# big-muff.net
KiCad netlist of a schematic drawn in EAGLE
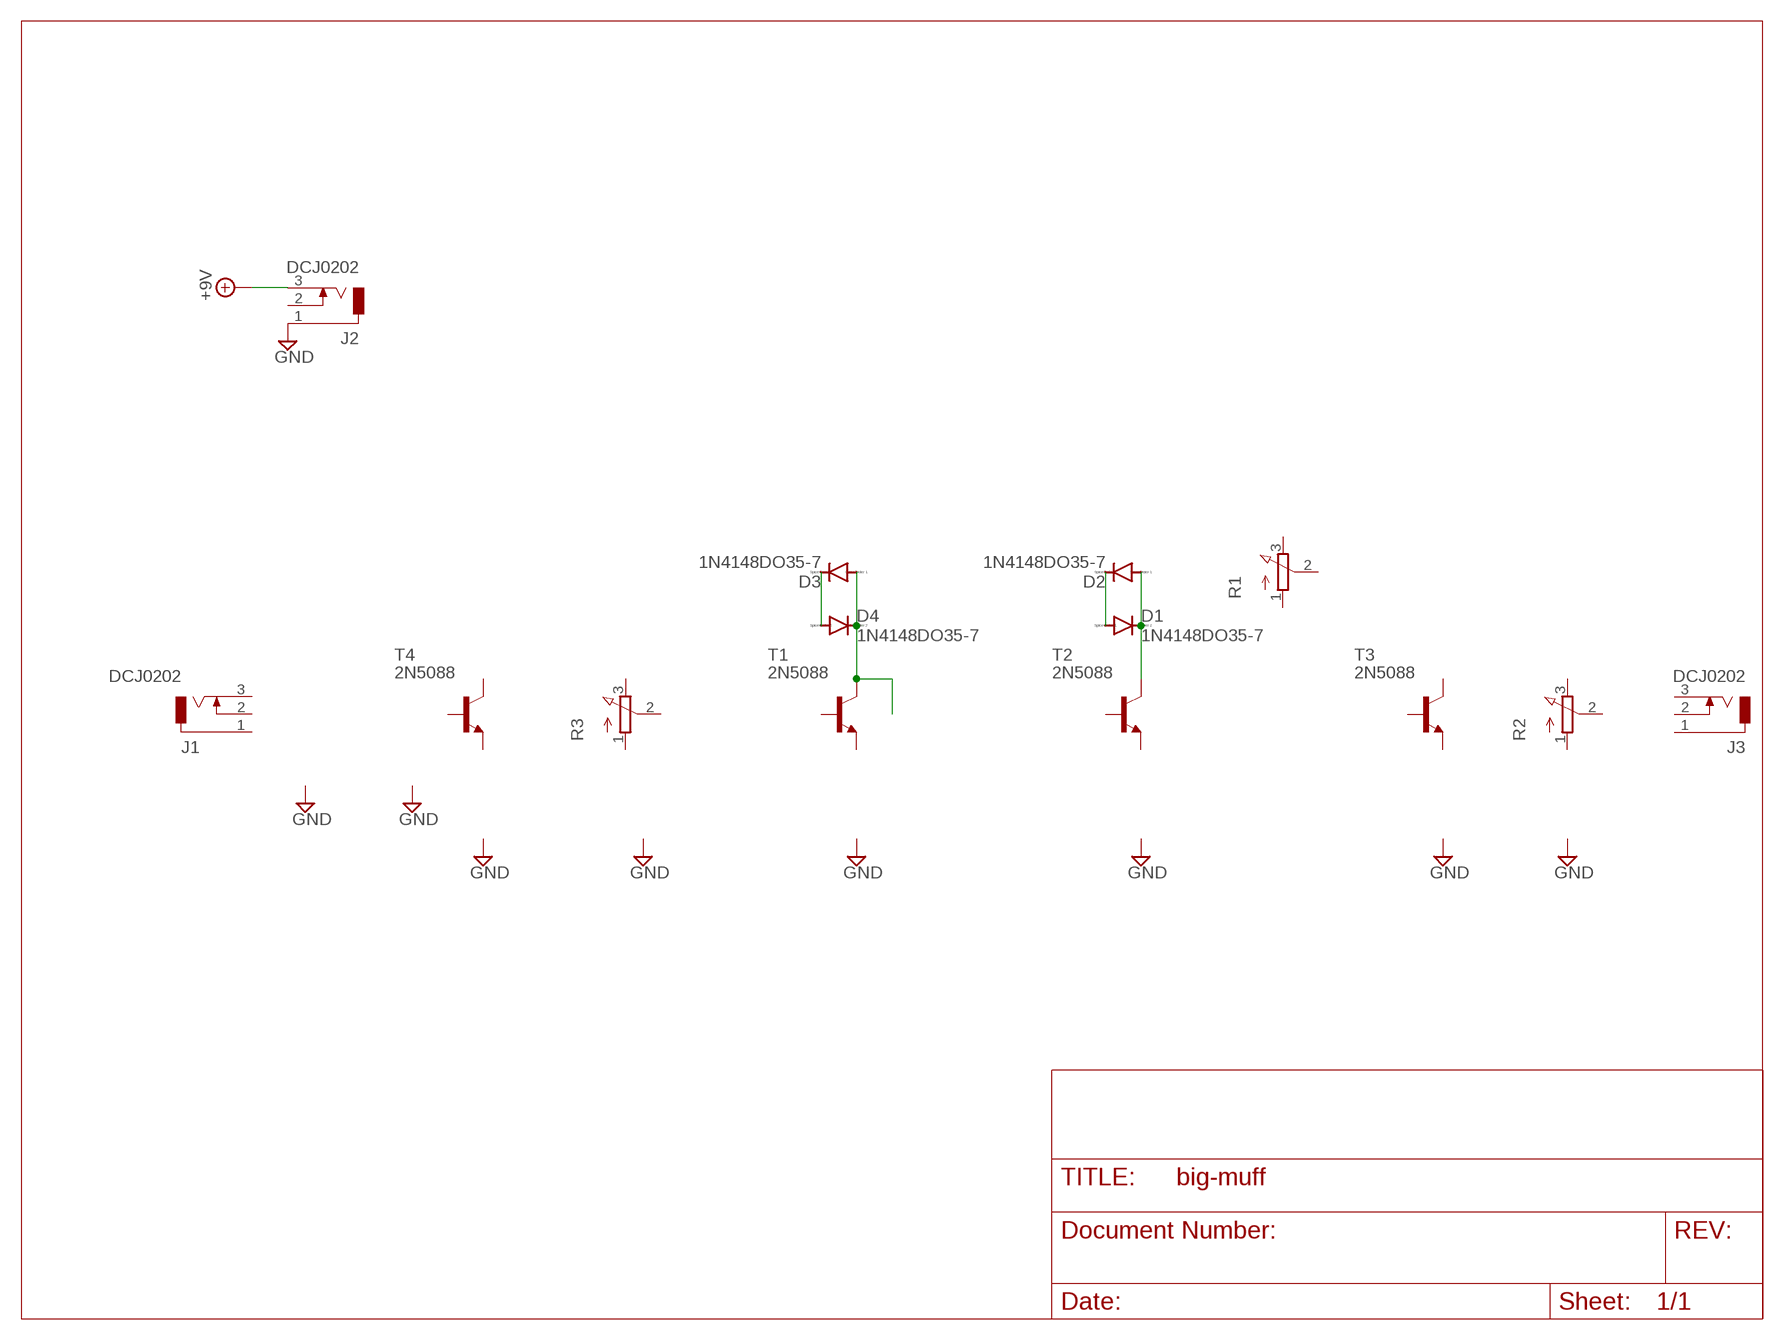
[diagram p0: schematic, sheet 1]

(export (version "E")
  (design (tool "Eeschema 10.0.6"))
  (components
    (comp (ref "D1")
      (value "1N4148DO35-7")
      (footprint "eagle-import:DO35-7")
      (libsource (lib "eagle-import") (part "1N4148DO35-7"))
    )
    (comp (ref "D2")
      (value "1N4148DO35-7")
      (footprint "eagle-import:DO35-7")
      (libsource (lib "eagle-import") (part "1N4148DO35-7"))
    )
    (comp (ref "D3")
      (value "1N4148DO35-7")
      (footprint "eagle-import:DO35-7")
      (libsource (lib "eagle-import") (part "1N4148DO35-7"))
    )
    (comp (ref "D4")
      (value "1N4148DO35-7")
      (footprint "eagle-import:DO35-7")
      (libsource (lib "eagle-import") (part "1N4148DO35-7"))
    )
    (comp (ref "J1")
      (value "DCJ0202")
      (footprint "eagle-import:DCJ0202")
      (libsource (lib "eagle-import") (part "DCJ0202"))
    )
    (comp (ref "J2")
      (value "DCJ0202")
      (footprint "eagle-import:DCJ0202")
      (libsource (lib "eagle-import") (part "DCJ0202"))
    )
    (comp (ref "J3")
      (value "DCJ0202")
      (footprint "eagle-import:DCJ0202")
      (libsource (lib "eagle-import") (part "DCJ0202"))
    )
    (comp (ref "R1")
      (value "3RP/1610N")
      (footprint "eagle-import:3RP_1610N")
      (libsource (lib "eagle-import") (part "3RP/1610N"))
    )
    (comp (ref "R2")
      (value "3RP/1610N")
      (footprint "eagle-import:3RP_1610N")
      (libsource (lib "eagle-import") (part "3RP/1610N"))
    )
    (comp (ref "R3")
      (value "3RP/1610N")
      (footprint "eagle-import:3RP_1610N")
      (libsource (lib "eagle-import") (part "3RP/1610N"))
    )
    (comp (ref "T1")
      (value "2N5088")
      (footprint "eagle-import:TO92")
      (libsource (lib "eagle-import") (part "2N5088"))
    )
    (comp (ref "T2")
      (value "2N5088")
      (footprint "eagle-import:TO92")
      (libsource (lib "eagle-import") (part "2N5088"))
    )
    (comp (ref "T3")
      (value "2N5088")
      (footprint "eagle-import:TO92")
      (libsource (lib "eagle-import") (part "2N5088"))
    )
    (comp (ref "T4")
      (value "2N5088")
      (footprint "eagle-import:TO92")
      (libsource (lib "eagle-import") (part "2N5088"))
    )
  )
  (nets
    (net (code "1") (name "+9V") (class "Default")
      (node (ref "J2") (pin "3") (pinfunction "3_3") (pintype "passive"))
    )
    (net (code "2") (name "GND") (class "Default")
      (node (ref "J2") (pin "1") (pinfunction "1_1") (pintype "passive"))
    )
    (net (code "3") (name "Net-(D1-PadA)") (class "Default")
      (node (ref "D1") (pin "A") (pinfunction "A_A") (pintype "passive"))
      (node (ref "D2") (pin "C") (pinfunction "C_C") (pintype "passive"))
    )
    (net (code "4") (name "Net-(D3-PadC)") (class "Default")
      (node (ref "D3") (pin "C") (pinfunction "C_C") (pintype "passive"))
      (node (ref "D4") (pin "A") (pinfunction "A_A") (pintype "passive"))
    )
    (net (code "5") (name "Net-(T1-C)") (class "Default")
      (node (ref "D3") (pin "A") (pinfunction "A_A") (pintype "passive"))
      (node (ref "D4") (pin "C") (pinfunction "C_C") (pintype "passive"))
      (node (ref "T1") (pin "1") (pinfunction "C_1") (pintype "passive"))
    )
    (net (code "6") (name "Net-(T2-C)") (class "Default")
      (node (ref "D1") (pin "C") (pinfunction "C_C") (pintype "passive"))
      (node (ref "D2") (pin "A") (pinfunction "A_A") (pintype "passive"))
      (node (ref "T2") (pin "1") (pinfunction "C_1") (pintype "passive"))
    )
    (net (code "7") (name "unconnected-(J1-Pad1)") (class "Default")
      (node (ref "J1") (pin "1") (pinfunction "1_1") (pintype "passive"))
    )
    (net (code "8") (name "unconnected-(J1-Pad2)") (class "Default")
      (node (ref "J1") (pin "2") (pinfunction "2_2") (pintype "passive"))
    )
    (net (code "9") (name "unconnected-(J1-Pad3)") (class "Default")
      (node (ref "J1") (pin "3") (pinfunction "3_3") (pintype "passive"))
    )
    (net (code "10") (name "unconnected-(J2-Pad2)") (class "Default")
      (node (ref "J2") (pin "2") (pinfunction "2_2") (pintype "passive"))
    )
    (net (code "11") (name "unconnected-(J3-Pad1)") (class "Default")
      (node (ref "J3") (pin "1") (pinfunction "1_1") (pintype "passive"))
    )
    (net (code "12") (name "unconnected-(J3-Pad2)") (class "Default")
      (node (ref "J3") (pin "2") (pinfunction "2_2") (pintype "passive"))
    )
    (net (code "13") (name "unconnected-(J3-Pad3)") (class "Default")
      (node (ref "J3") (pin "3") (pinfunction "3_3") (pintype "passive"))
    )
    (net (code "14") (name "unconnected-(R1-A-Pad1)") (class "Default")
      (node (ref "R1") (pin "1") (pinfunction "A_1") (pintype "passive"))
    )
    (net (code "15") (name "unconnected-(R1-E-Pad3)") (class "Default")
      (node (ref "R1") (pin "3") (pinfunction "E_3") (pintype "passive"))
    )
    (net (code "16") (name "unconnected-(R1-S-Pad2)") (class "Default")
      (node (ref "R1") (pin "2") (pinfunction "S_2") (pintype "passive"))
    )
    (net (code "17") (name "unconnected-(R2-A-Pad1)") (class "Default")
      (node (ref "R2") (pin "1") (pinfunction "A_1") (pintype "passive"))
    )
    (net (code "18") (name "unconnected-(R2-E-Pad3)") (class "Default")
      (node (ref "R2") (pin "3") (pinfunction "E_3") (pintype "passive"))
    )
    (net (code "19") (name "unconnected-(R2-S-Pad2)") (class "Default")
      (node (ref "R2") (pin "2") (pinfunction "S_2") (pintype "passive"))
    )
    (net (code "20") (name "unconnected-(R3-A-Pad1)") (class "Default")
      (node (ref "R3") (pin "1") (pinfunction "A_1") (pintype "passive"))
    )
    (net (code "21") (name "unconnected-(R3-E-Pad3)") (class "Default")
      (node (ref "R3") (pin "3") (pinfunction "E_3") (pintype "passive"))
    )
    (net (code "22") (name "unconnected-(R3-S-Pad2)") (class "Default")
      (node (ref "R3") (pin "2") (pinfunction "S_2") (pintype "passive"))
    )
    (net (code "23") (name "unconnected-(T1-B-Pad2)") (class "Default")
      (node (ref "T1") (pin "2") (pinfunction "B_2") (pintype "passive"))
    )
    (net (code "24") (name "unconnected-(T1-E-Pad3)") (class "Default")
      (node (ref "T1") (pin "3") (pinfunction "E_3") (pintype "passive"))
    )
    (net (code "25") (name "unconnected-(T2-B-Pad2)") (class "Default")
      (node (ref "T2") (pin "2") (pinfunction "B_2") (pintype "passive"))
    )
    (net (code "26") (name "unconnected-(T2-E-Pad3)") (class "Default")
      (node (ref "T2") (pin "3") (pinfunction "E_3") (pintype "passive"))
    )
    (net (code "27") (name "unconnected-(T3-B-Pad2)") (class "Default")
      (node (ref "T3") (pin "2") (pinfunction "B_2") (pintype "passive"))
    )
    (net (code "28") (name "unconnected-(T3-C-Pad1)") (class "Default")
      (node (ref "T3") (pin "1") (pinfunction "C_1") (pintype "passive"))
    )
    (net (code "29") (name "unconnected-(T3-E-Pad3)") (class "Default")
      (node (ref "T3") (pin "3") (pinfunction "E_3") (pintype "passive"))
    )
    (net (code "30") (name "unconnected-(T4-B-Pad2)") (class "Default")
      (node (ref "T4") (pin "2") (pinfunction "B_2") (pintype "passive"))
    )
    (net (code "31") (name "unconnected-(T4-C-Pad1)") (class "Default")
      (node (ref "T4") (pin "1") (pinfunction "C_1") (pintype "passive"))
    )
    (net (code "32") (name "unconnected-(T4-E-Pad3)") (class "Default")
      (node (ref "T4") (pin "3") (pinfunction "E_3") (pintype "passive"))
    )
  )
)
